# Sheet1.net
KiCad netlist of a schematic drawn in Altium Designer
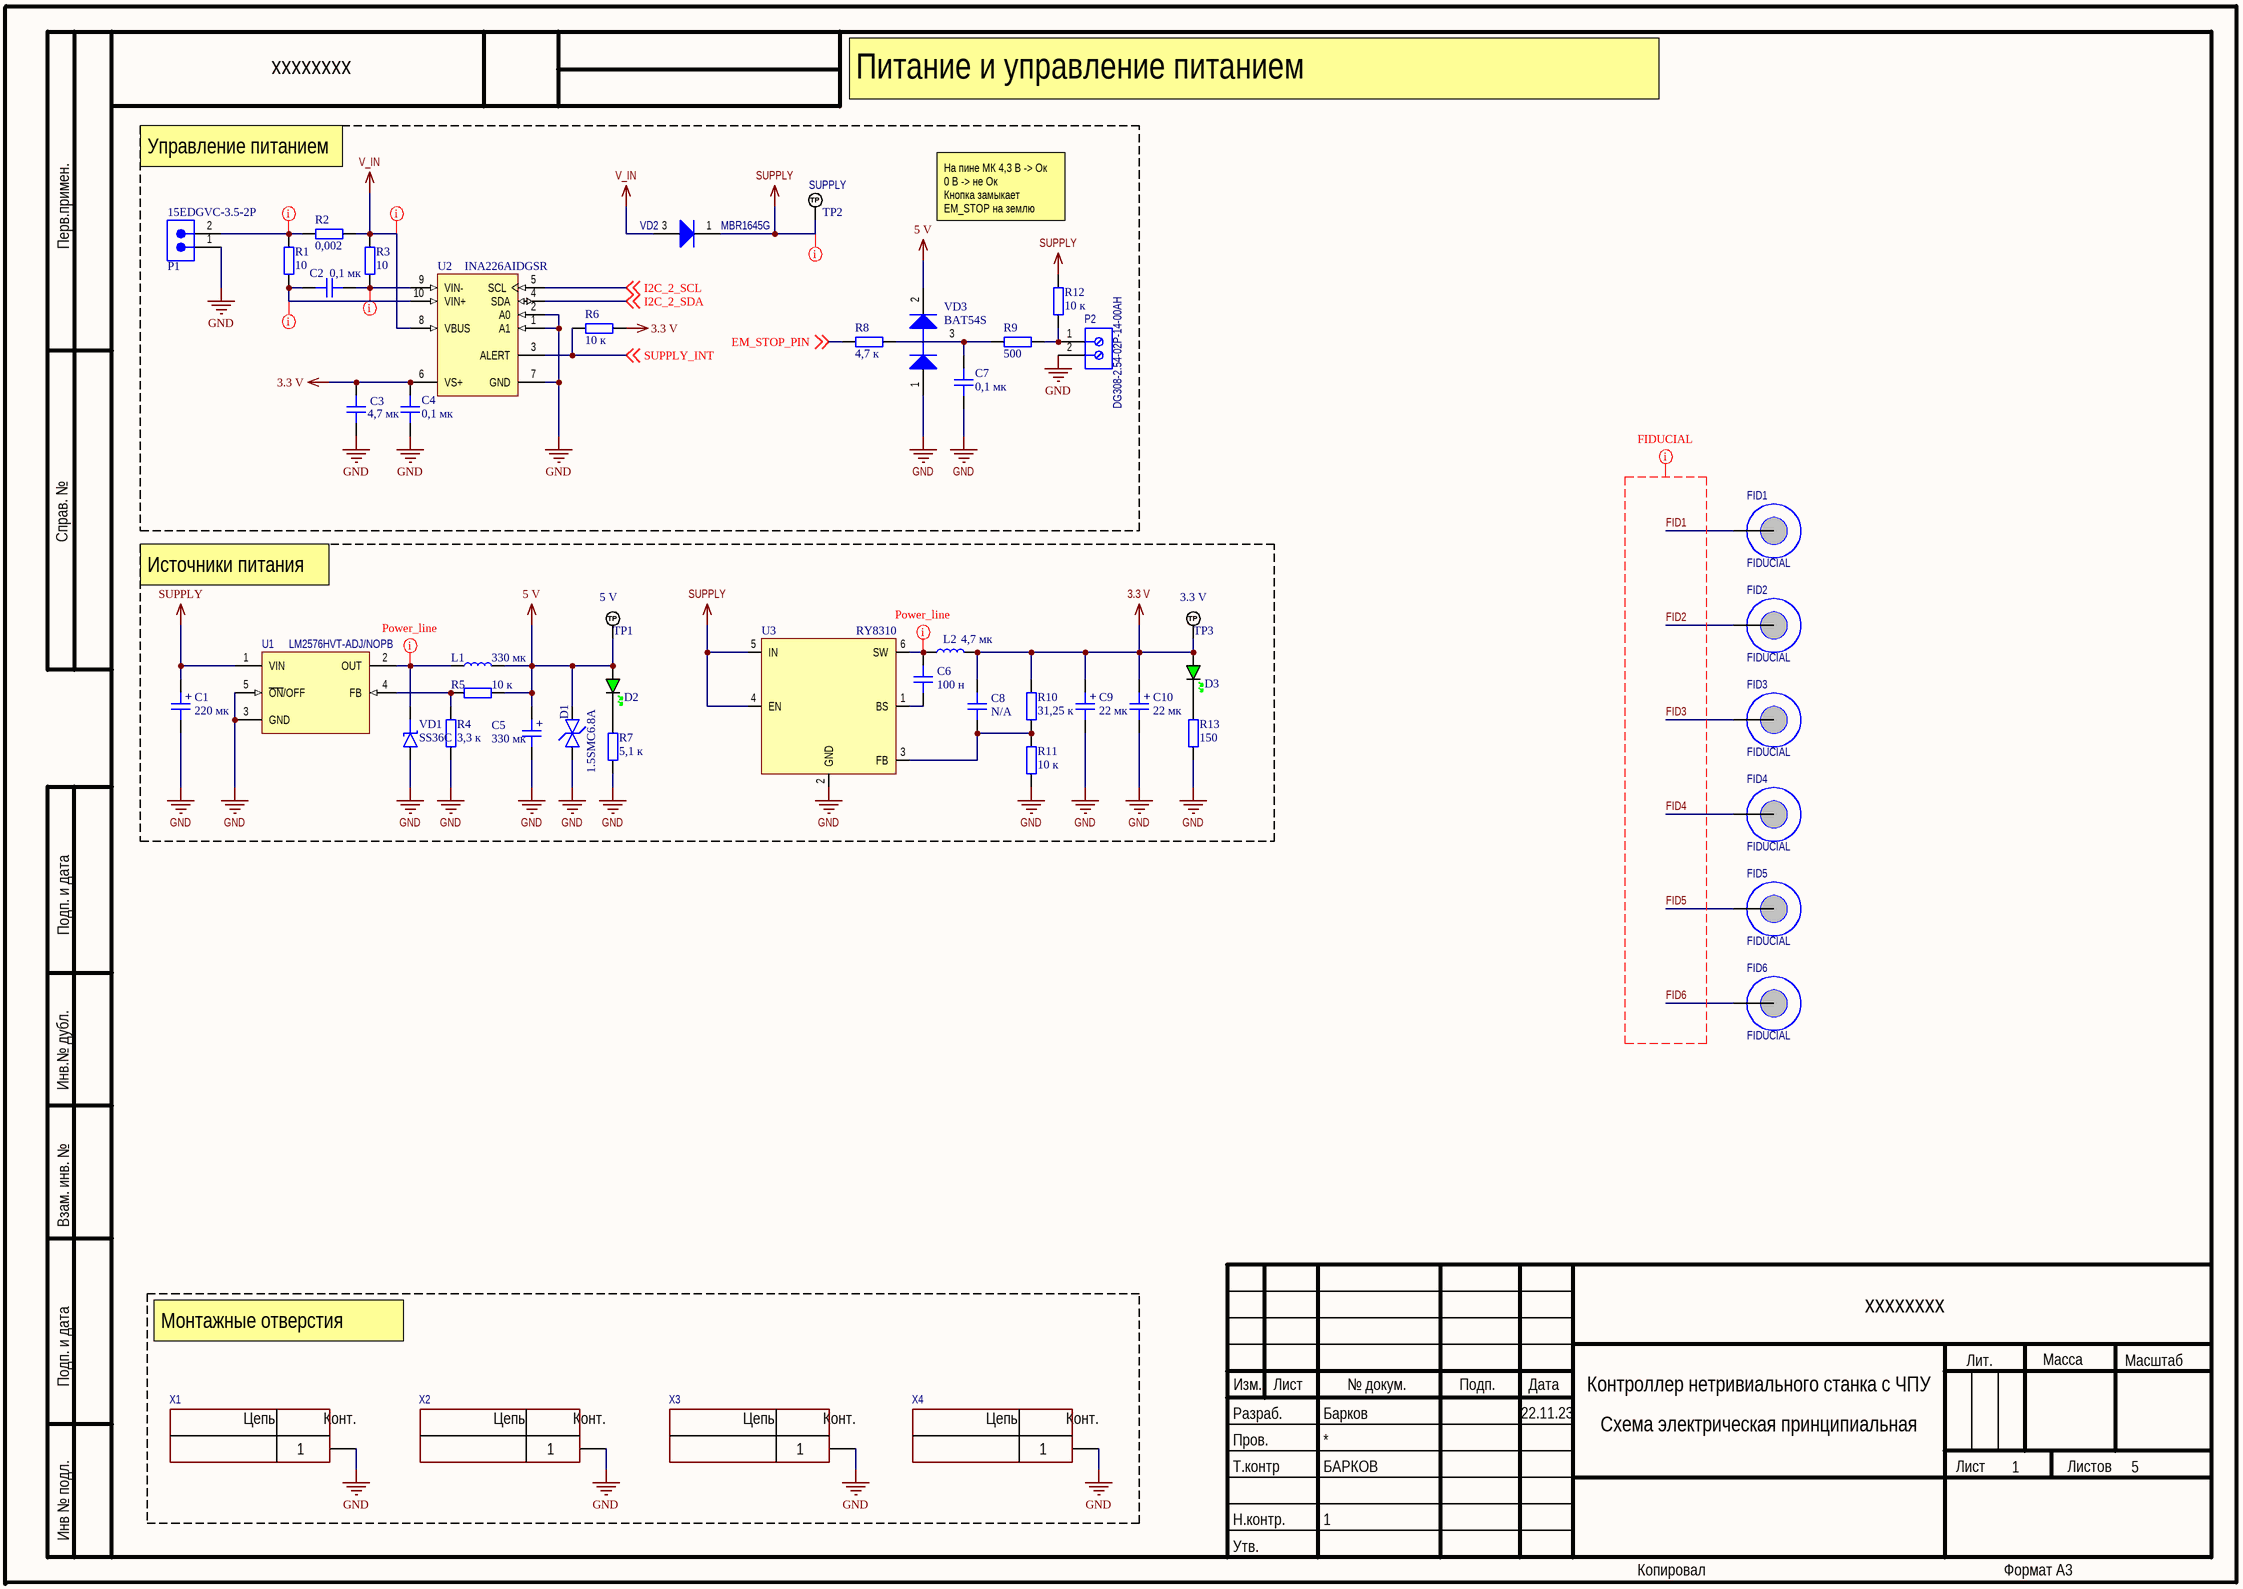
[diagram p0: Sheet1.SchDoc]

(export (version "E")
  (design (tool "Eeschema 10.0.6"))
  (components
    (comp (ref "C1")
      (value "220 мк")
      (footprint "D10C5H12.5")
      (description "Электролитический конденсатор")
      (fields (field (name "VOLTAGE") "50"))
      (libsource (lib "Schematic-Lib-PhilsLab") (part "CAP_ALEL_16x16.5_25V"))
    )
    (comp (ref "C2")
      (value "0,1 мк")
      (footprint "CAP_0603")
      (description "Керамический конденсатор")
      (libsource (lib "Schematic-Lib-PhilsLab") (part "CAP_0603"))
    )
    (comp (ref "C3")
      (value "4,7 мк")
      (footprint "CAP_0805")
      (description "Керамический конденсатор")
      (libsource (lib "Schematic-Lib-PhilsLab") (part "CAP_0805"))
    )
    (comp (ref "C4")
      (value "0,1 мк")
      (footprint "CAP_0603")
      (description "Керамический конденсатор")
      (libsource (lib "Schematic-Lib-PhilsLab") (part "CAP_0603"))
    )
    (comp (ref "C5")
      (value "330 мк")
      (footprint "D8C3.5H12")
      (description "Электролитический конденсатор")
      (fields (field (name "VOLTAGE") "16"))
      (libsource (lib "Schematic-Lib-PhilsLab") (part "CAP_ALEL_16x16.5_25V"))
    )
    (comp (ref "C6")
      (value "100 н")
      (footprint "CAP_0603")
      (description "Керамический конденсатор")
      (libsource (lib "Schematic-Lib-PhilsLab") (part "CAP_0805"))
    )
    (comp (ref "C7")
      (value "0,1 мк")
      (footprint "CAP_0603")
      (description "Керамический конденсатор")
      (libsource (lib "Schematic-Lib-PhilsLab") (part "CAP_0603"))
    )
    (comp (ref "C8")
      (value "N/A")
      (footprint "CAP_0603")
      (description "Керамический конденсатор")
      (libsource (lib "Schematic-Lib-PhilsLab") (part "CAP_0805"))
    )
    (comp (ref "C9")
      (value "22 мк")
      (footprint "TANTAL_B")
      (description "Танталовый конденсатор")
      (fields (field (name "VOLTAGE") "6,3"))
      (libsource (lib "Schematic-Lib-PhilsLab") (part "CAP_ALEL_16x16.5_25V"))
    )
    (comp (ref "C10")
      (value "22 мк")
      (footprint "TANTAL_B")
      (description "Танталовый конденсатор")
      (fields (field (name "VOLTAGE") "6,3"))
      (libsource (lib "Schematic-Lib-PhilsLab") (part "CAP_ALEL_16x16.5_25V"))
    )
    (comp (ref "D1")
      (value "1.5SMC6.8A")
      (footprint "SMC-DO-214AB")
      (description "Защитный диод")
      (libsource (lib "Schematic-Lib-PhilsLab") (part "D_TVS_BI_SMC"))
    )
    (comp (ref "D2")
      (value "GREEN")
      (footprint "LED_0603_GREEN")
      (description "Зелёный светодиод")
      (libsource (lib "Schematic-Lib-PhilsLab") (part "LED_0603_GREEN"))
    )
    (comp (ref "D3")
      (value "GREEN")
      (footprint "LED_0603_GREEN")
      (description "Зелёный светодиод")
      (libsource (lib "Schematic-Lib-PhilsLab") (part "LED_0603_GREEN"))
    )
    (comp (ref "FID1")
      (value "FIDUCIAL")
      (footprint "FIDUCIAL")
      (description "Реперная метка")
      (libsource (lib "BarkockLib") (part "FIDUCIAL"))
    )
    (comp (ref "FID2")
      (value "FIDUCIAL")
      (footprint "FIDUCIAL")
      (description "Реперная метка")
      (libsource (lib "BarkockLib") (part "FIDUCIAL"))
    )
    (comp (ref "FID3")
      (value "FIDUCIAL")
      (footprint "FIDUCIAL")
      (description "Реперная метка")
      (libsource (lib "BarkockLib") (part "FIDUCIAL"))
    )
    (comp (ref "FID4")
      (value "FIDUCIAL")
      (footprint "FIDUCIAL")
      (description "Реперная метка")
      (libsource (lib "BarkockLib") (part "FIDUCIAL"))
    )
    (comp (ref "FID5")
      (value "FIDUCIAL")
      (footprint "FIDUCIAL")
      (description "Реперная метка")
      (libsource (lib "BarkockLib") (part "FIDUCIAL"))
    )
    (comp (ref "FID6")
      (value "FIDUCIAL")
      (footprint "FIDUCIAL")
      (description "Реперная метка")
      (libsource (lib "BarkockLib") (part "FIDUCIAL"))
    )
    (comp (ref "L1")
      (value "330 мк")
      (footprint "IND: B82477G4")
      (description "Индуктор")
      (libsource (lib "Schematic-Lib-PhilsLab") (part "NRS5020"))
    )
    (comp (ref "L2")
      (value "4,7 мк")
      (footprint "NRS5020")
      (description "Индуктор")
      (libsource (lib "Schematic-Lib-PhilsLab") (part "NRS5020"))
    )
    (comp (ref "P1")
      (value "15EDGVC-3.5-2P")
      (footprint "691321100002")
      (description "Раъёмный винтовой клеммник")
      (libsource (lib "Altium Content Vault") (part "TBL - 1R - 02P - Male"))
    )
    (comp (ref "P2")
      (value "DG308-2.54-02P-14-00AH")
      (footprint "PHOE-1725656-2")
      (description "Винтовой клеммник")
      (libsource (lib "Altium Content Vault") (part "CN-1P-F-TB2"))
    )
    (comp (ref "R1")
      (value "10")
      (footprint "RES_0603")
      (description "Резистор")
      (libsource (lib "Schematic-Lib-PhilsLab") (part "RES_0603"))
    )
    (comp (ref "R2")
      (value "0,002")
      (footprint "ch2512r")
      (description "Резистор")
      (libsource (lib "Schematic-Lib-PhilsLab") (part "RES_0603"))
    )
    (comp (ref "R3")
      (value "10")
      (footprint "RES_0603")
      (description "Резистор")
      (libsource (lib "Schematic-Lib-PhilsLab") (part "RES_0603"))
    )
    (comp (ref "R4")
      (value "3,3 к")
      (footprint "RES_0603")
      (description "Резистор")
      (libsource (lib "Schematic-Lib-PhilsLab") (part "RES_0603"))
    )
    (comp (ref "R5")
      (value "10 к")
      (footprint "RES_0603")
      (description "Резистор")
      (libsource (lib "Schematic-Lib-PhilsLab") (part "RES_0603"))
    )
    (comp (ref "R6")
      (value "10 к")
      (footprint "RES_0603")
      (description "Резистор")
      (libsource (lib "Schematic-Lib-PhilsLab") (part "RES_0603"))
    )
    (comp (ref "R7")
      (value "5,1 к")
      (footprint "RES_0603")
      (description "Резистор")
      (libsource (lib "Schematic-Lib-PhilsLab") (part "RES_0603"))
    )
    (comp (ref "R8")
      (value "4,7 к")
      (footprint "RES_0603")
      (description "Резистор")
      (libsource (lib "Schematic-Lib-PhilsLab") (part "RES_0603"))
    )
    (comp (ref "R9")
      (value "500")
      (footprint "RES_0603")
      (description "Резистор")
      (libsource (lib "Schematic-Lib-PhilsLab") (part "RES_0603"))
    )
    (comp (ref "R10")
      (value "31,25 к")
      (footprint "RES_0603")
      (description "Резистор")
      (libsource (lib "Schematic-Lib-PhilsLab") (part "RES_0805"))
    )
    (comp (ref "R11")
      (value "10 к")
      (footprint "RES_0603")
      (description "Резистор")
      (libsource (lib "Schematic-Lib-PhilsLab") (part "RES_0805"))
    )
    (comp (ref "R12")
      (value "10 к")
      (footprint "RES_0603")
      (description "Резистор")
      (libsource (lib "Schematic-Lib-PhilsLab") (part "RES_0603"))
    )
    (comp (ref "R13")
      (value "150")
      (footprint "RES_0603")
      (description "Резистор")
      (libsource (lib "Schematic-Lib-PhilsLab") (part "RES_0603"))
    )
    (comp (ref "TP1")
      (value "5 V")
      (footprint "PAD_RND_1MM")
      (libsource (lib "Schematic-Lib-PhilsLab") (part "TEST_POINT_RND_1MM"))
    )
    (comp (ref "TP2")
      (value "SUPPLY")
      (footprint "PAD_RND_1MM")
      (libsource (lib "Schematic-Lib-PhilsLab") (part "TEST_POINT_RND_1MM"))
    )
    (comp (ref "TP3")
      (value "3.3 V")
      (footprint "PAD_RND_1MM")
      (libsource (lib "Schematic-Lib-PhilsLab") (part "TEST_POINT_RND_1MM"))
    )
    (comp (ref "U1")
      (value "LM2576HVT-ADJ/NOPB")
      (footprint "KC0005A")
      (description "Понижающий DC-DC")
      (libsource (lib "Altium Content Vault") (part "PM-REG-LM2575HVT-12"))
    )
    (comp (ref "U2")
      (value "INA226AIDGSR")
      (footprint "DGS0010A_L")
      (description "Измеритель мощности")
      (libsource (lib "Altium Content Vault") (part "TI-INA226DGS10"))
    )
    (comp (ref "U3")
      (value "RY8310")
      (footprint "SOT-23-6")
      (description "Понижающий DC-DC")
      (libsource (lib "Schematic-Lib-PhilsLab") (part "MT2492"))
    )
    (comp (ref "VD1")
      (value "SS36C")
      (footprint "SMC-DO-214AB")
      (description "Диод")
      (libsource (lib "Schematic-Lib-PhilsLab") (part "D_SCHOTTKY_SMC"))
    )
    (comp (ref "VD2")
      (value "MBR1645G")
      (footprint "ONSC-TO-220-2-221B-04_E")
      (description "Мощный диод")
      (libsource (lib "Altium Content Vault") (part "ONSC-D-K1A3-2_A"))
    )
    (comp (ref "VD3")
      (value "BAT54S")
      (footprint "ONSC-SOT-323-3-419-04_V")
      (description "Пара последовательных диодов")
      (libsource (lib "Altium Content Vault") (part "ONSC-D-A1K2C3-3"))
    )
    (comp (ref "X1")
      (value "*")
      (footprint "CON: PADS 1x3mm")
      (libsource (lib "Connectors") (part "1-Connector"))
    )
    (comp (ref "X2")
      (value "*")
      (footprint "CON: PADS 1x3mm")
      (libsource (lib "Connectors") (part "1-Connector"))
    )
    (comp (ref "X3")
      (value "*")
      (footprint "CON: PADS 1x3mm")
      (libsource (lib "Connectors") (part "1-Connector"))
    )
    (comp (ref "X4")
      (value "*")
      (footprint "CON: PADS 1x3mm")
      (libsource (lib "Connectors") (part "1-Connector"))
    )
  )
  (nets
    (net (code "1") (name "/FID1") (class "Default")
      (node (ref "FID1") (pin "1") (pinfunction "1_1") (pintype "passive"))
    )
    (net (code "2") (name "/FID2") (class "Default")
      (node (ref "FID2") (pin "1") (pinfunction "1_1") (pintype "passive"))
    )
    (net (code "3") (name "/FID3") (class "Default")
      (node (ref "FID3") (pin "1") (pinfunction "1_1") (pintype "passive"))
    )
    (net (code "4") (name "/FID4") (class "Default")
      (node (ref "FID4") (pin "1") (pinfunction "1_1") (pintype "passive"))
    )
    (net (code "5") (name "/FID5") (class "Default")
      (node (ref "FID5") (pin "1") (pinfunction "1_1") (pintype "passive"))
    )
    (net (code "6") (name "/FID6") (class "Default")
      (node (ref "FID6") (pin "1") (pinfunction "1_1") (pintype "passive"))
    )
    (net (code "7") (name "3.3 V") (class "Default")
      (node (ref "C10") (pin "1") (pinfunction "1_1") (pintype "passive"))
      (node (ref "C3") (pin "2") (pinfunction "2_2") (pintype "passive"))
      (node (ref "C4") (pin "1") (pinfunction "1_1") (pintype "passive"))
      (node (ref "C8") (pin "2") (pinfunction "2_2") (pintype "passive"))
      (node (ref "C9") (pin "1") (pinfunction "1_1") (pintype "passive"))
      (node (ref "D3") (pin "A") (pinfunction "A_A") (pintype "passive"))
      (node (ref "L2") (pin "2") (pinfunction "2_2") (pintype "passive"))
      (node (ref "R10") (pin "1") (pinfunction "1_1") (pintype "passive"))
      (node (ref "R6") (pin "2") (pinfunction "2_2") (pintype "passive"))
      (node (ref "TP3") (pin "1") (pinfunction "TP_1") (pintype "passive"))
      (node (ref "U2") (pin "6") (pinfunction "VS+_6") (pintype "power_in"))
    )
    (net (code "8") (name "5 V") (class "Default")
      (node (ref "C5") (pin "1") (pinfunction "1_1") (pintype "passive"))
      (node (ref "D1") (pin "K") (pinfunction "K_K") (pintype "passive"))
      (node (ref "D2") (pin "A") (pinfunction "A_A") (pintype "passive"))
      (node (ref "L1") (pin "2") (pinfunction "2_2") (pintype "passive"))
      (node (ref "R5") (pin "1") (pinfunction "1_1") (pintype "passive"))
      (node (ref "TP1") (pin "1") (pinfunction "TP_1") (pintype "passive"))
      (node (ref "VD3") (pin "2") (pinfunction "K_2") (pintype "passive"))
    )
    (net (code "9") (name "EM_STOP_PIN") (class "Default")
      (node (ref "R8") (pin "2") (pinfunction "2_2") (pintype "passive"))
    )
    (net (code "10") (name "GND") (class "Default")
      (node (ref "C1") (pin "2") (pinfunction "2_2") (pintype "passive"))
      (node (ref "C10") (pin "2") (pinfunction "2_2") (pintype "passive"))
      (node (ref "C3") (pin "1") (pinfunction "1_1") (pintype "passive"))
      (node (ref "C4") (pin "2") (pinfunction "2_2") (pintype "passive"))
      (node (ref "C5") (pin "2") (pinfunction "2_2") (pintype "passive"))
      (node (ref "C7") (pin "2") (pinfunction "2_2") (pintype "passive"))
      (node (ref "C9") (pin "2") (pinfunction "2_2") (pintype "passive"))
      (node (ref "D1") (pin "A") (pinfunction "A_A") (pintype "passive"))
      (node (ref "P1") (pin "1") (pinfunction "1_1") (pintype "passive"))
      (node (ref "P2") (pin "2") (pinfunction "2_2") (pintype "passive"))
      (node (ref "R11") (pin "2") (pinfunction "2_2") (pintype "passive"))
      (node (ref "R13") (pin "1") (pinfunction "1_1") (pintype "passive"))
      (node (ref "R4") (pin "1") (pinfunction "1_1") (pintype "passive"))
      (node (ref "R7") (pin "1") (pinfunction "1_1") (pintype "passive"))
      (node (ref "U1") (pin "3") (pinfunction "GND_3") (pintype "power_in"))
      (node (ref "U1") (pin "5") (pinfunction "~{ON}/OFF_5") (pintype "input"))
      (node (ref "U2") (pin "1") (pinfunction "A1_1") (pintype "input"))
      (node (ref "U2") (pin "2") (pinfunction "A0_2") (pintype "input"))
      (node (ref "U2") (pin "7") (pinfunction "GND_7") (pintype "power_in"))
      (node (ref "U3") (pin "2") (pinfunction "GND_2") (pintype "passive"))
      (node (ref "VD1") (pin "A") (pinfunction "A_A") (pintype "passive"))
      (node (ref "VD3") (pin "1") (pinfunction "A_1") (pintype "passive"))
      (node (ref "X1") (pin "1") (pinfunction "1_1") (pintype "passive"))
      (node (ref "X2") (pin "1") (pinfunction "1_1") (pintype "passive"))
      (node (ref "X3") (pin "1") (pinfunction "1_1") (pintype "passive"))
      (node (ref "X4") (pin "1") (pinfunction "1_1") (pintype "passive"))
    )
    (net (code "11") (name "I2C_2_SCL") (class "Default")
      (node (ref "U2") (pin "5") (pinfunction "SCL_5") (pintype "input"))
    )
    (net (code "12") (name "I2C_2_SDA") (class "Default")
      (node (ref "U2") (pin "4") (pinfunction "SDA_4") (pintype "bidirectional"))
    )
    (net (code "13") (name "Net-(D2-PadK)") (class "Default")
      (node (ref "D2") (pin "K") (pinfunction "K_K") (pintype "passive"))
      (node (ref "R7") (pin "2") (pinfunction "2_2") (pintype "passive"))
    )
    (net (code "14") (name "Net-(D3-PadK)") (class "Default")
      (node (ref "D3") (pin "K") (pinfunction "K_K") (pintype "passive"))
      (node (ref "R13") (pin "2") (pinfunction "2_2") (pintype "passive"))
    )
    (net (code "15") (name "Net-(P1-Pad2)") (class "Default")
      (node (ref "P1") (pin "2") (pinfunction "2_2") (pintype "passive"))
      (node (ref "R1") (pin "1") (pinfunction "1_1") (pintype "passive"))
      (node (ref "R2") (pin "1") (pinfunction "1_1") (pintype "passive"))
    )
    (net (code "16") (name "Net-(P2-Pad1)") (class "Default")
      (node (ref "P2") (pin "1") (pinfunction "1_1") (pintype "passive"))
      (node (ref "R12") (pin "1") (pinfunction "1_1") (pintype "passive"))
      (node (ref "R9") (pin "1") (pinfunction "1_1") (pintype "passive"))
    )
    (net (code "17") (name "Net-(U1-FB)") (class "Default")
      (node (ref "R4") (pin "2") (pinfunction "2_2") (pintype "passive"))
      (node (ref "R5") (pin "2") (pinfunction "2_2") (pintype "passive"))
      (node (ref "U1") (pin "4") (pinfunction "FB_4") (pintype "input"))
    )
    (net (code "18") (name "Net-(U1-OUT)") (class "Default")
      (node (ref "L1") (pin "1") (pinfunction "1_1") (pintype "passive"))
      (node (ref "U1") (pin "2") (pinfunction "OUT_2") (pintype "power_in"))
      (node (ref "VD1") (pin "K") (pinfunction "K_K") (pintype "passive"))
    )
    (net (code "19") (name "Net-(U2-VIN+)") (class "Default")
      (node (ref "C2") (pin "2") (pinfunction "2_2") (pintype "passive"))
      (node (ref "R1") (pin "2") (pinfunction "2_2") (pintype "passive"))
      (node (ref "U2") (pin "10") (pinfunction "VIN+_10") (pintype "input"))
    )
    (net (code "20") (name "Net-(U2-VIN-)") (class "Default")
      (node (ref "C2") (pin "1") (pinfunction "1_1") (pintype "passive"))
      (node (ref "R3") (pin "2") (pinfunction "2_2") (pintype "passive"))
      (node (ref "U2") (pin "9") (pinfunction "VIN-_9") (pintype "input"))
    )
    (net (code "21") (name "Net-(U3-BS)") (class "Default")
      (node (ref "C6") (pin "1") (pinfunction "1_1") (pintype "passive"))
      (node (ref "U3") (pin "1") (pinfunction "BS_1") (pintype "passive"))
    )
    (net (code "22") (name "Net-(U3-FB)") (class "Default")
      (node (ref "C8") (pin "1") (pinfunction "1_1") (pintype "passive"))
      (node (ref "R10") (pin "2") (pinfunction "2_2") (pintype "passive"))
      (node (ref "R11") (pin "1") (pinfunction "1_1") (pintype "passive"))
      (node (ref "U3") (pin "3") (pinfunction "FB_3") (pintype "passive"))
    )
    (net (code "23") (name "Net-(U3-SW)") (class "Default")
      (node (ref "C6") (pin "2") (pinfunction "2_2") (pintype "passive"))
      (node (ref "L2") (pin "1") (pinfunction "1_1") (pintype "passive"))
      (node (ref "U3") (pin "6") (pinfunction "SW_6") (pintype "passive"))
    )
    (net (code "24") (name "Net-(VD3-K{slash}A)") (class "Default")
      (node (ref "C7") (pin "1") (pinfunction "1_1") (pintype "passive"))
      (node (ref "R8") (pin "1") (pinfunction "1_1") (pintype "passive"))
      (node (ref "R9") (pin "2") (pinfunction "2_2") (pintype "passive"))
      (node (ref "VD3") (pin "3") (pinfunction "K/A_3") (pintype "passive"))
    )
    (net (code "25") (name "SUPPLY") (class "Default")
      (node (ref "C1") (pin "1") (pinfunction "1_1") (pintype "passive"))
      (node (ref "R12") (pin "2") (pinfunction "2_2") (pintype "passive"))
      (node (ref "TP2") (pin "1") (pinfunction "TP_1") (pintype "passive"))
      (node (ref "U1") (pin "1") (pinfunction "VIN_1") (pintype "power_in"))
      (node (ref "U3") (pin "4") (pinfunction "EN_4") (pintype "passive"))
      (node (ref "U3") (pin "5") (pinfunction "IN_5") (pintype "passive"))
      (node (ref "VD2") (pin "1") (pinfunction "K_1") (pintype "passive"))
    )
    (net (code "26") (name "SUPPLY_INT") (class "Default")
      (node (ref "R6") (pin "1") (pinfunction "1_1") (pintype "passive"))
      (node (ref "U2") (pin "3") (pinfunction "ALERT_3") (pintype "open_collector"))
    )
    (net (code "27") (name "V_IN") (class "Default")
      (node (ref "R2") (pin "2") (pinfunction "2_2") (pintype "passive"))
      (node (ref "R3") (pin "1") (pinfunction "1_1") (pintype "passive"))
      (node (ref "U2") (pin "8") (pinfunction "VBUS_8") (pintype "input"))
      (node (ref "VD2") (pin "3") (pinfunction "A_3") (pintype "passive"))
    )
  )
)
